# RN52_Breakout_07-27-16.net
KiCad netlist of a schematic drawn in EAGLE
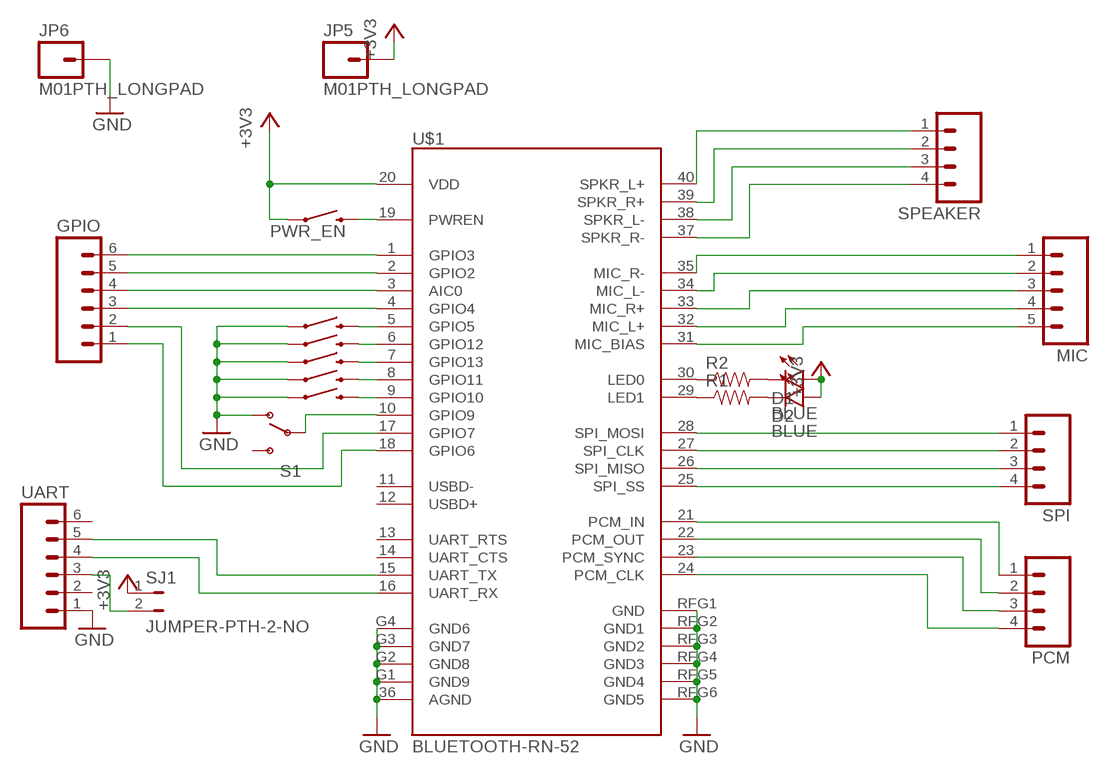
[diagram p0: schematic, sheet 1]

(export (version "E")
  (design (tool "Eeschema 10.0.6"))
  (components
    (comp (ref "D1")
      (value "BLUE")
      (footprint "eagle-import:LED-1206")
      (libsource (lib "eagle-import") (part "LED-BLUE1206"))
    )
    (comp (ref "D2")
      (value "BLUE")
      (footprint "eagle-import:LED-1206")
      (libsource (lib "eagle-import") (part "LED-BLUE1206"))
    )
    (comp (ref "GPIO")
      (value "M06LONGPADS")
      (footprint "eagle-import:1X06_LONGPADS")
      (libsource (lib "eagle-import") (part "M06LONGPADS"))
    )
    (comp (ref "JP5")
      (value "M01PTH_LONGPAD")
      (footprint "eagle-import:1X01_LONGPAD")
      (libsource (lib "eagle-import") (part "M01PTH_LONGPAD"))
    )
    (comp (ref "JP6")
      (value "M01PTH_LONGPAD")
      (footprint "eagle-import:1X01_LONGPAD")
      (libsource (lib "eagle-import") (part "M01PTH_LONGPAD"))
    )
    (comp (ref "MIC")
      (value "M05PTH_LONGPADS")
      (footprint "eagle-import:1X05_LONGPADS")
      (libsource (lib "eagle-import") (part "M05PTH_LONGPADS"))
    )
    (comp (ref "PCM")
      (value "M04LONGPADS")
      (footprint "eagle-import:1X04_LONGPADS")
      (libsource (lib "eagle-import") (part "M04LONGPADS"))
    )
    (comp (ref "PWR_EN")
      (value "SWITCH-MOMENTARY-2PTH")
      (footprint "eagle-import:TACTILE-PTH")
      (libsource (lib "eagle-import") (part "SWITCH-MOMENTARY-2PTH"))
    )
    (comp (ref "PWR_EN1")
      (value "SWITCH-MOMENTARY-2PTH")
      (footprint "eagle-import:TACTILE-PTH")
      (libsource (lib "eagle-import") (part "SWITCH-MOMENTARY-2PTH"))
    )
    (comp (ref "PWR_EN2")
      (value "SWITCH-MOMENTARY-2PTH")
      (footprint "eagle-import:TACTILE-PTH")
      (libsource (lib "eagle-import") (part "SWITCH-MOMENTARY-2PTH"))
    )
    (comp (ref "PWR_EN3")
      (value "SWITCH-MOMENTARY-2PTH")
      (footprint "eagle-import:TACTILE-PTH")
      (libsource (lib "eagle-import") (part "SWITCH-MOMENTARY-2PTH"))
    )
    (comp (ref "PWR_EN4")
      (value "SWITCH-MOMENTARY-2PTH")
      (footprint "eagle-import:TACTILE-PTH")
      (libsource (lib "eagle-import") (part "SWITCH-MOMENTARY-2PTH"))
    )
    (comp (ref "PWR_EN5")
      (value "SWITCH-MOMENTARY-2PTH")
      (footprint "eagle-import:TACTILE-PTH")
      (libsource (lib "eagle-import") (part "SWITCH-MOMENTARY-2PTH"))
    )
    (comp (ref "R1")
      (value "3.3MOHM-1/10W-1%(0603)")
      (footprint "eagle-import:0603-RES")
      (libsource (lib "eagle-import") (part "3.3MOHM-1/10W-1%(0603)"))
    )
    (comp (ref "R2")
      (value "3.3MOHM-1/10W-1%(0603)")
      (footprint "eagle-import:0603-RES")
      (libsource (lib "eagle-import") (part "3.3MOHM-1/10W-1%(0603)"))
    )
    (comp (ref "S1")
      (value "SWITCH-SPDTPTH")
      (footprint "eagle-import:SWITCH-SPDT")
      (libsource (lib "eagle-import") (part "SWITCH-SPDTPTH"))
    )
    (comp (ref "SJ1")
      (value "JUMPER-PTH-2-NO")
      (footprint "eagle-import:PTH-JUMPER-2-NO_NO_SILK")
      (libsource (lib "eagle-import") (part "JUMPER-PTH-2-NO"))
    )
    (comp (ref "SPEAKER")
      (value "M04LONGPADS")
      (footprint "eagle-import:1X04_LONGPADS")
      (libsource (lib "eagle-import") (part "M04LONGPADS"))
    )
    (comp (ref "SPI")
      (value "M04LONGPADS")
      (footprint "eagle-import:1X04_LONGPADS")
      (libsource (lib "eagle-import") (part "M04LONGPADS"))
    )
    (comp (ref "U$1")
      (value "BLUETOOTH-RN-52")
      (footprint "eagle-import:RN-52")
      (libsource (lib "eagle-import") (part "BLUETOOTH-RN-52"))
    )
    (comp (ref "UART")
      (value "M06LONGPADS")
      (footprint "eagle-import:1X06_LONGPADS")
      (libsource (lib "eagle-import") (part "M06LONGPADS"))
    )
  )
  (nets
    (net (code "1") (name "+3V3") (class "Default")
      (node (ref "D1") (pin "A") (pinfunction "A_A") (pintype "passive"))
      (node (ref "D2") (pin "A") (pinfunction "A_A") (pintype "passive"))
      (node (ref "JP5") (pin "1") (pinfunction "1_1") (pintype "passive"))
      (node (ref "PWR_EN") (pin "1") (pinfunction "1_1") (pintype "passive"))
      (node (ref "SJ1") (pin "1") (pinfunction "1_1") (pintype "passive"))
      (node (ref "U$1") (pin "20") (pinfunction "VDD_20") (pintype "bidirectional"))
    )
    (net (code "2") (name "GND") (class "Default")
      (node (ref "JP6") (pin "1") (pinfunction "1_1") (pintype "passive"))
      (node (ref "PWR_EN1") (pin "1") (pinfunction "1_1") (pintype "passive"))
      (node (ref "PWR_EN2") (pin "1") (pinfunction "1_1") (pintype "passive"))
      (node (ref "PWR_EN3") (pin "1") (pinfunction "1_1") (pintype "passive"))
      (node (ref "PWR_EN4") (pin "1") (pinfunction "1_1") (pintype "passive"))
      (node (ref "PWR_EN5") (pin "1") (pinfunction "1_1") (pintype "passive"))
      (node (ref "S1") (pin "1") (pinfunction "O_1") (pintype "passive"))
      (node (ref "U$1") (pin "36") (pinfunction "AGND_36") (pintype "bidirectional"))
      (node (ref "U$1") (pin "G1") (pinfunction "GND9_G1") (pintype "bidirectional"))
      (node (ref "U$1") (pin "G2") (pinfunction "GND8_G2") (pintype "bidirectional"))
      (node (ref "U$1") (pin "G3") (pinfunction "GND7_G3") (pintype "bidirectional"))
      (node (ref "U$1") (pin "G4") (pinfunction "GND6_G4") (pintype "bidirectional"))
      (node (ref "U$1") (pin "RFG1") (pinfunction "GND_RFG1") (pintype "bidirectional"))
      (node (ref "U$1") (pin "RFG2") (pinfunction "GND1_RFG2") (pintype "bidirectional"))
      (node (ref "U$1") (pin "RFG3") (pinfunction "GND2_RFG3") (pintype "bidirectional"))
      (node (ref "U$1") (pin "RFG4") (pinfunction "GND3_RFG4") (pintype "bidirectional"))
      (node (ref "U$1") (pin "RFG5") (pinfunction "GND4_RFG5") (pintype "bidirectional"))
      (node (ref "U$1") (pin "RFG6") (pinfunction "GND5_RFG6") (pintype "bidirectional"))
      (node (ref "UART") (pin "1") (pinfunction "1_1") (pintype "passive"))
    )
    (net (code "3") (name "Net-(D1-PadC)") (class "Default")
      (node (ref "D1") (pin "C") (pinfunction "C_C") (pintype "passive"))
      (node (ref "R2") (pin "2") (pinfunction "2_2") (pintype "passive"))
    )
    (net (code "4") (name "Net-(D2-PadC)") (class "Default")
      (node (ref "D2") (pin "C") (pinfunction "C_C") (pintype "passive"))
      (node (ref "R1") (pin "2") (pinfunction "2_2") (pintype "passive"))
    )
    (net (code "5") (name "Net-(PWR_EN-2)") (class "Default")
      (node (ref "PWR_EN") (pin "3") (pinfunction "2_3") (pintype "passive"))
      (node (ref "U$1") (pin "19") (pinfunction "PWREN_19") (pintype "bidirectional"))
    )
    (net (code "6") (name "Net-(PWR_EN1-2)") (class "Default")
      (node (ref "PWR_EN1") (pin "3") (pinfunction "2_3") (pintype "passive"))
      (node (ref "U$1") (pin "5") (pinfunction "GPIO5_5") (pintype "bidirectional"))
    )
    (net (code "7") (name "Net-(PWR_EN2-2)") (class "Default")
      (node (ref "PWR_EN2") (pin "3") (pinfunction "2_3") (pintype "passive"))
      (node (ref "U$1") (pin "6") (pinfunction "GPIO12_6") (pintype "bidirectional"))
    )
    (net (code "8") (name "Net-(PWR_EN3-2)") (class "Default")
      (node (ref "PWR_EN3") (pin "3") (pinfunction "2_3") (pintype "passive"))
      (node (ref "U$1") (pin "7") (pinfunction "GPIO13_7") (pintype "bidirectional"))
    )
    (net (code "9") (name "Net-(PWR_EN4-2)") (class "Default")
      (node (ref "PWR_EN4") (pin "3") (pinfunction "2_3") (pintype "passive"))
      (node (ref "U$1") (pin "8") (pinfunction "GPIO11_8") (pintype "bidirectional"))
    )
    (net (code "10") (name "Net-(PWR_EN5-2)") (class "Default")
      (node (ref "PWR_EN5") (pin "3") (pinfunction "2_3") (pintype "passive"))
      (node (ref "U$1") (pin "9") (pinfunction "GPIO10_9") (pintype "bidirectional"))
    )
    (net (code "11") (name "Net-(S1-P)") (class "Default")
      (node (ref "S1") (pin "2") (pinfunction "P_2") (pintype "passive"))
      (node (ref "U$1") (pin "10") (pinfunction "GPIO9_10") (pintype "bidirectional"))
    )
    (net (code "12") (name "Net-(SJ1-Pad2)") (class "Default")
      (node (ref "SJ1") (pin "2") (pinfunction "2_2") (pintype "passive"))
      (node (ref "UART") (pin "3") (pinfunction "3_3") (pintype "passive"))
    )
    (net (code "13") (name "Net-(U$1-AIC0)") (class "Default")
      (node (ref "GPIO") (pin "4") (pinfunction "4_4") (pintype "passive"))
      (node (ref "U$1") (pin "3") (pinfunction "AIC0_3") (pintype "bidirectional"))
    )
    (net (code "14") (name "Net-(U$1-GPIO2)") (class "Default")
      (node (ref "GPIO") (pin "5") (pinfunction "5_5") (pintype "passive"))
      (node (ref "U$1") (pin "2") (pinfunction "GPIO2_2") (pintype "bidirectional"))
    )
    (net (code "15") (name "Net-(U$1-GPIO3)") (class "Default")
      (node (ref "GPIO") (pin "6") (pinfunction "6_6") (pintype "passive"))
      (node (ref "U$1") (pin "1") (pinfunction "GPIO3_1") (pintype "bidirectional"))
    )
    (net (code "16") (name "Net-(U$1-GPIO4)") (class "Default")
      (node (ref "GPIO") (pin "3") (pinfunction "3_3") (pintype "passive"))
      (node (ref "U$1") (pin "4") (pinfunction "GPIO4_4") (pintype "bidirectional"))
    )
    (net (code "17") (name "Net-(U$1-GPIO6)") (class "Default")
      (node (ref "GPIO") (pin "1") (pinfunction "1_1") (pintype "passive"))
      (node (ref "U$1") (pin "18") (pinfunction "GPIO6_18") (pintype "bidirectional"))
    )
    (net (code "18") (name "Net-(U$1-GPIO7)") (class "Default")
      (node (ref "GPIO") (pin "2") (pinfunction "2_2") (pintype "passive"))
      (node (ref "U$1") (pin "17") (pinfunction "GPIO7_17") (pintype "bidirectional"))
    )
    (net (code "19") (name "Net-(U$1-LED0)") (class "Default")
      (node (ref "R2") (pin "1") (pinfunction "1_1") (pintype "passive"))
      (node (ref "U$1") (pin "30") (pinfunction "LED0_30") (pintype "bidirectional"))
    )
    (net (code "20") (name "Net-(U$1-LED1)") (class "Default")
      (node (ref "R1") (pin "1") (pinfunction "1_1") (pintype "passive"))
      (node (ref "U$1") (pin "29") (pinfunction "LED1_29") (pintype "bidirectional"))
    )
    (net (code "21") (name "Net-(U$1-MIC_BIAS)") (class "Default")
      (node (ref "MIC") (pin "5") (pinfunction "5_5") (pintype "passive"))
      (node (ref "U$1") (pin "31") (pinfunction "MIC_BIAS_31") (pintype "bidirectional"))
    )
    (net (code "22") (name "Net-(U$1-MIC_L+)") (class "Default")
      (node (ref "MIC") (pin "4") (pinfunction "4_4") (pintype "passive"))
      (node (ref "U$1") (pin "32") (pinfunction "MIC_L+_32") (pintype "bidirectional"))
    )
    (net (code "23") (name "Net-(U$1-MIC_L-)") (class "Default")
      (node (ref "MIC") (pin "2") (pinfunction "2_2") (pintype "passive"))
      (node (ref "U$1") (pin "34") (pinfunction "MIC_L-_34") (pintype "bidirectional"))
    )
    (net (code "24") (name "Net-(U$1-MIC_R+)") (class "Default")
      (node (ref "MIC") (pin "3") (pinfunction "3_3") (pintype "passive"))
      (node (ref "U$1") (pin "33") (pinfunction "MIC_R+_33") (pintype "bidirectional"))
    )
    (net (code "25") (name "Net-(U$1-MIC_R-)") (class "Default")
      (node (ref "MIC") (pin "1") (pinfunction "1_1") (pintype "passive"))
      (node (ref "U$1") (pin "35") (pinfunction "MIC_R-_35") (pintype "bidirectional"))
    )
    (net (code "26") (name "Net-(U$1-PCM_CLK)") (class "Default")
      (node (ref "PCM") (pin "4") (pinfunction "4_4") (pintype "passive"))
      (node (ref "U$1") (pin "24") (pinfunction "PCM_CLK_24") (pintype "bidirectional"))
    )
    (net (code "27") (name "Net-(U$1-PCM_IN)") (class "Default")
      (node (ref "PCM") (pin "1") (pinfunction "1_1") (pintype "passive"))
      (node (ref "U$1") (pin "21") (pinfunction "PCM_IN_21") (pintype "bidirectional"))
    )
    (net (code "28") (name "Net-(U$1-PCM_OUT)") (class "Default")
      (node (ref "PCM") (pin "2") (pinfunction "2_2") (pintype "passive"))
      (node (ref "U$1") (pin "22") (pinfunction "PCM_OUT_22") (pintype "bidirectional"))
    )
    (net (code "29") (name "Net-(U$1-PCM_SYNC)") (class "Default")
      (node (ref "PCM") (pin "3") (pinfunction "3_3") (pintype "passive"))
      (node (ref "U$1") (pin "23") (pinfunction "PCM_SYNC_23") (pintype "bidirectional"))
    )
    (net (code "30") (name "Net-(U$1-SPI_CLK)") (class "Default")
      (node (ref "SPI") (pin "2") (pinfunction "2_2") (pintype "passive"))
      (node (ref "U$1") (pin "27") (pinfunction "SPI_CLK_27") (pintype "bidirectional"))
    )
    (net (code "31") (name "Net-(U$1-SPI_MISO)") (class "Default")
      (node (ref "SPI") (pin "3") (pinfunction "3_3") (pintype "passive"))
      (node (ref "U$1") (pin "26") (pinfunction "SPI_MISO_26") (pintype "bidirectional"))
    )
    (net (code "32") (name "Net-(U$1-SPI_MOSI)") (class "Default")
      (node (ref "SPI") (pin "1") (pinfunction "1_1") (pintype "passive"))
      (node (ref "U$1") (pin "28") (pinfunction "SPI_MOSI_28") (pintype "bidirectional"))
    )
    (net (code "33") (name "Net-(U$1-SPI_SS)") (class "Default")
      (node (ref "SPI") (pin "4") (pinfunction "4_4") (pintype "passive"))
      (node (ref "U$1") (pin "25") (pinfunction "SPI_SS_25") (pintype "bidirectional"))
    )
    (net (code "34") (name "Net-(U$1-SPKR_L+)") (class "Default")
      (node (ref "SPEAKER") (pin "1") (pinfunction "1_1") (pintype "passive"))
      (node (ref "U$1") (pin "40") (pinfunction "SPKR_L+_40") (pintype "bidirectional"))
    )
    (net (code "35") (name "Net-(U$1-SPKR_L-)") (class "Default")
      (node (ref "SPEAKER") (pin "3") (pinfunction "3_3") (pintype "passive"))
      (node (ref "U$1") (pin "38") (pinfunction "SPKR_L-_38") (pintype "bidirectional"))
    )
    (net (code "36") (name "Net-(U$1-SPKR_R+)") (class "Default")
      (node (ref "SPEAKER") (pin "2") (pinfunction "2_2") (pintype "passive"))
      (node (ref "U$1") (pin "39") (pinfunction "SPKR_R+_39") (pintype "bidirectional"))
    )
    (net (code "37") (name "Net-(U$1-SPKR_R-)") (class "Default")
      (node (ref "SPEAKER") (pin "4") (pinfunction "4_4") (pintype "passive"))
      (node (ref "U$1") (pin "37") (pinfunction "SPKR_R-_37") (pintype "bidirectional"))
    )
    (net (code "38") (name "Net-(U$1-UART_RX)") (class "Default")
      (node (ref "U$1") (pin "16") (pinfunction "UART_RX_16") (pintype "bidirectional"))
      (node (ref "UART") (pin "4") (pinfunction "4_4") (pintype "passive"))
    )
    (net (code "39") (name "Net-(U$1-UART_TX)") (class "Default")
      (node (ref "U$1") (pin "15") (pinfunction "UART_TX_15") (pintype "bidirectional"))
      (node (ref "UART") (pin "5") (pinfunction "5_5") (pintype "passive"))
    )
    (net (code "40") (name "unconnected-(S1-S-Pad3)") (class "Default")
      (node (ref "S1") (pin "3") (pinfunction "S_3") (pintype "passive"))
    )
    (net (code "41") (name "unconnected-(U$1-UART_CTS-Pad14)") (class "Default")
      (node (ref "U$1") (pin "14") (pinfunction "UART_CTS_14") (pintype "bidirectional"))
    )
    (net (code "42") (name "unconnected-(U$1-UART_RTS-Pad13)") (class "Default")
      (node (ref "U$1") (pin "13") (pinfunction "UART_RTS_13") (pintype "bidirectional"))
    )
    (net (code "43") (name "unconnected-(U$1-USBD+-Pad12)") (class "Default")
      (node (ref "U$1") (pin "12") (pinfunction "USBD+_12") (pintype "bidirectional"))
    )
    (net (code "44") (name "unconnected-(U$1-USBD--Pad11)") (class "Default")
      (node (ref "U$1") (pin "11") (pinfunction "USBD-_11") (pintype "bidirectional"))
    )
    (net (code "45") (name "unconnected-(UART-Pad2)") (class "Default")
      (node (ref "UART") (pin "2") (pinfunction "2_2") (pintype "passive"))
    )
    (net (code "46") (name "unconnected-(UART-Pad6)") (class "Default")
      (node (ref "UART") (pin "6") (pinfunction "6_6") (pintype "passive"))
    )
  )
)
